# BLE112_Breakout_Board_v2_2.net
KiCad netlist of a schematic drawn in EAGLE
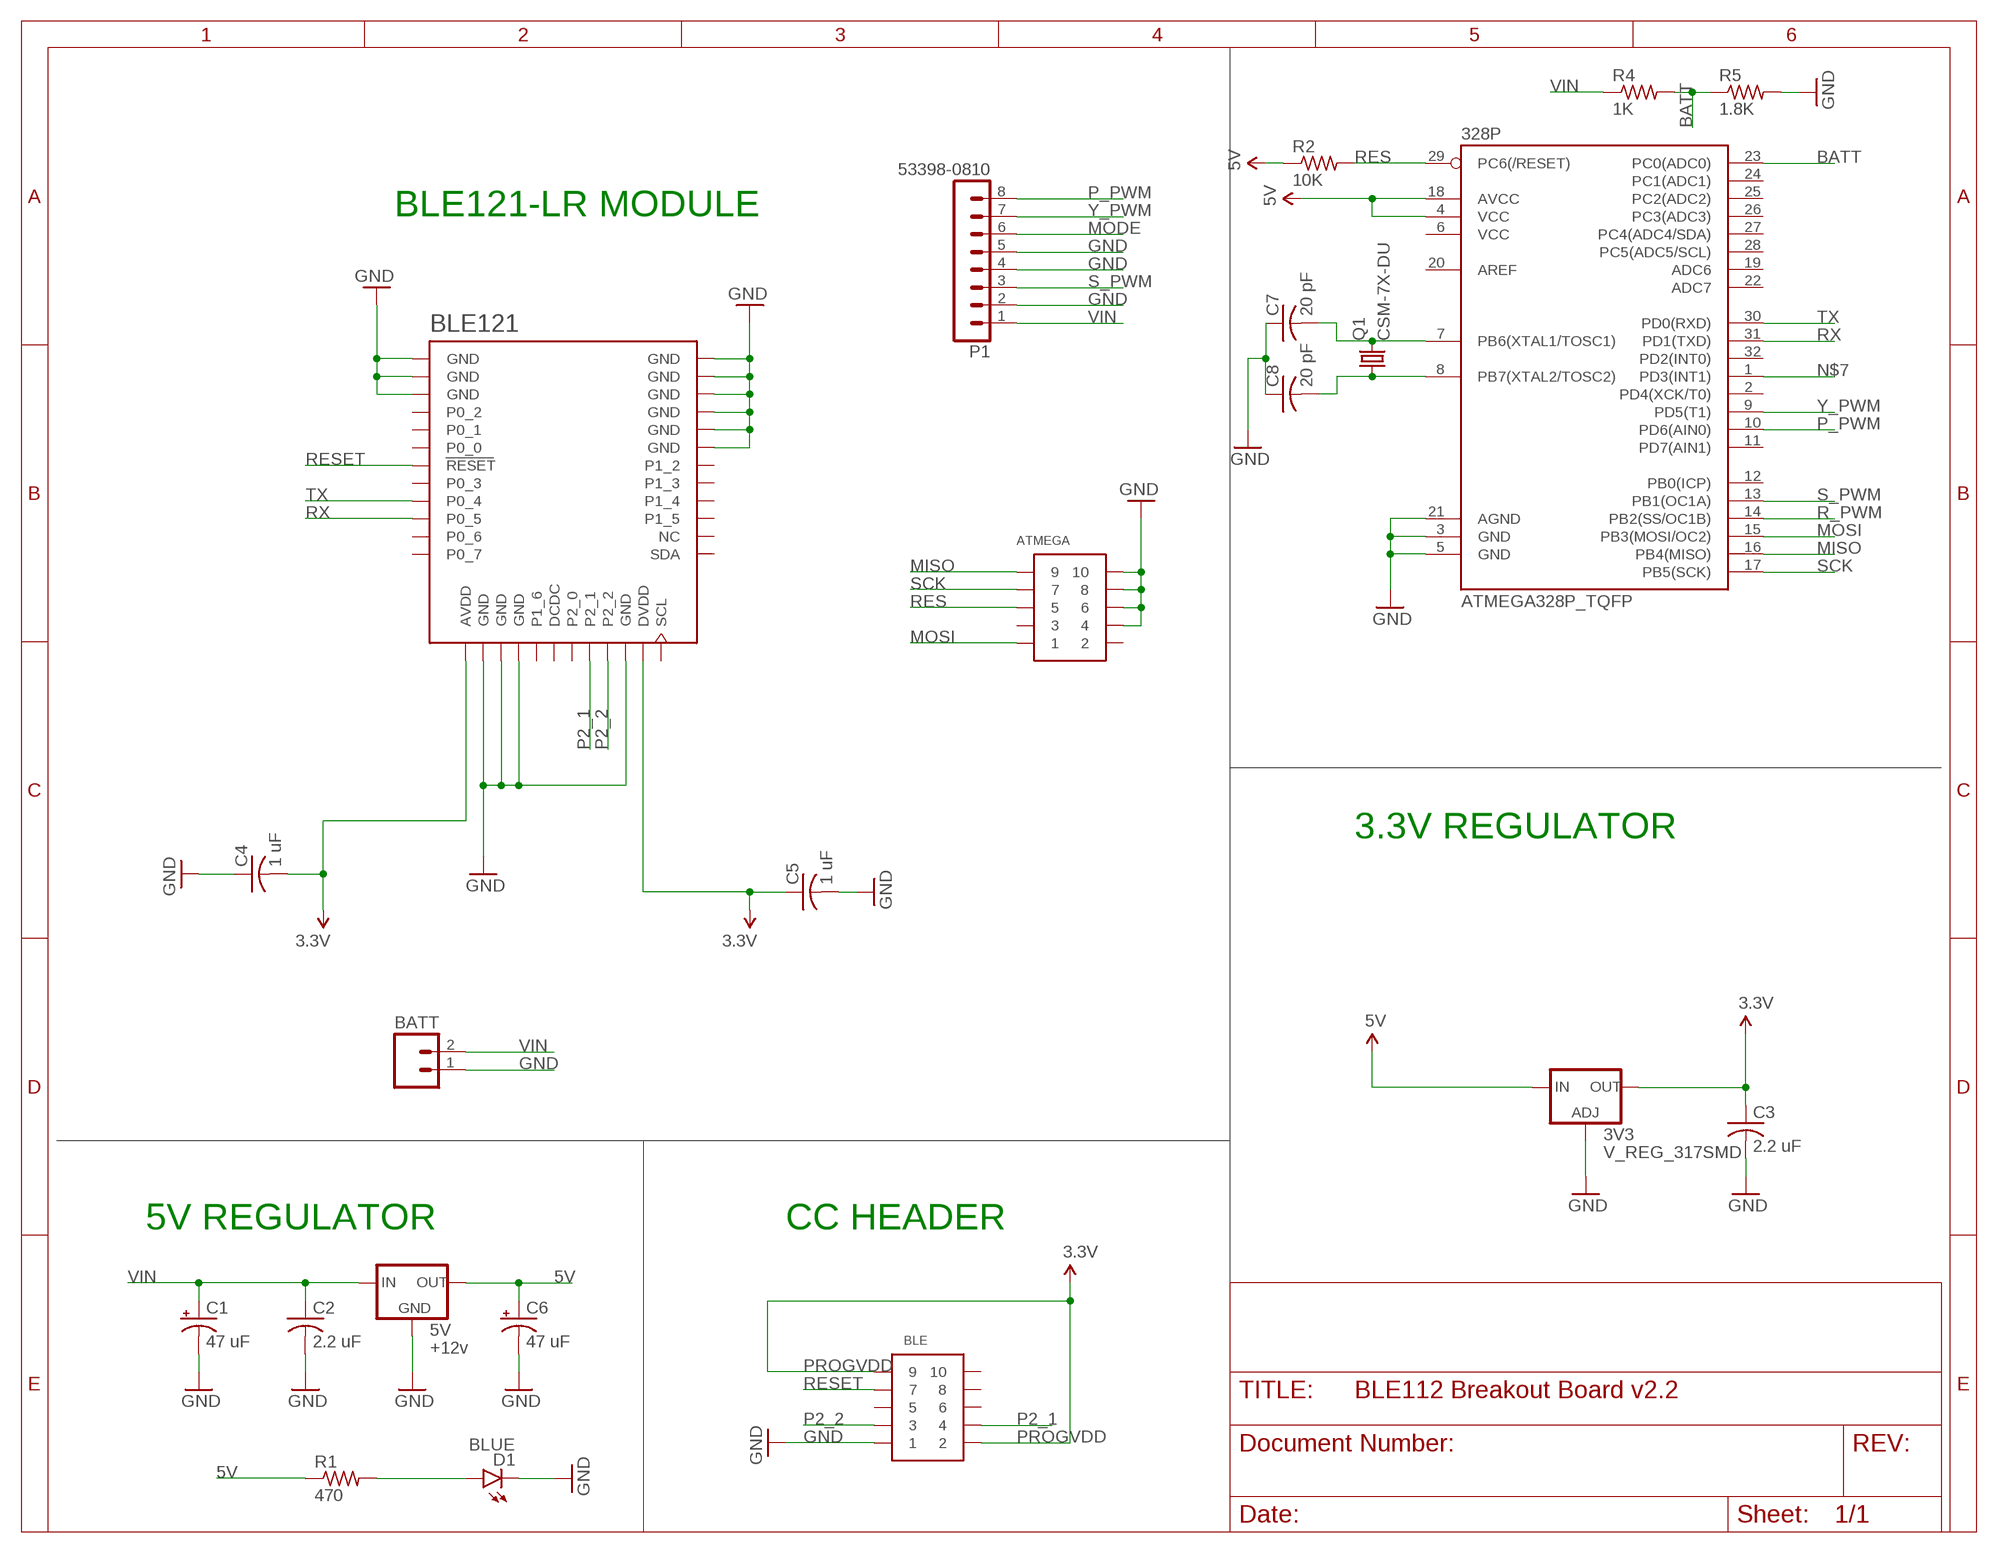
[diagram p0: schematic, sheet 1]

(export (version "E")
  (design (tool "Eeschema 10.0.6"))
  (components
    (comp (ref "3V3")
      (value "V_REG_317SMD")
      (footprint "eagle-import:SOT223")
      (libsource (lib "eagle-import") (part "V_REG_317SMD"))
    )
    (comp (ref "5V")
      (value "+12v")
      (footprint "eagle-import:TO-252")
      (libsource (lib "eagle-import") (part "V_REG_78XX7812"))
    )
    (comp (ref "328P")
      (value "ATMEGA328P_TQFP")
      (footprint "eagle-import:TQFP32-08")
      (libsource (lib "eagle-import") (part "ATMEGA328P_TQFP"))
    )
    (comp (ref "ATMEGA")
      (value "CONN_5-2-FTSH-V")
      (footprint "eagle-import:FTSH-105-DV")
      (libsource (lib "eagle-import") (part "CONN_5-2-FTSH-V"))
    )
    (comp (ref "BATT")
      (value "M02JST-PTH-2")
      (footprint "eagle-import:JST-2-PTH")
      (libsource (lib "eagle-import") (part "M02JST-PTH-2"))
    )
    (comp (ref "BLE")
      (value "CONN_5-2-FTSH-V")
      (footprint "eagle-import:FTSH-105-DV")
      (libsource (lib "eagle-import") (part "CONN_5-2-FTSH-V"))
    )
    (comp (ref "BLE121")
      (value "BLE121LR-VISUAL-A")
      (footprint "eagle-import:BLE121LR-A")
      (libsource (lib "eagle-import") (part "BLE121LR-VISUAL-A"))
    )
    (comp (ref "C1")
      (value "47 uF")
      (footprint "eagle-import:153CLV-0405")
      (libsource (lib "eagle-import") (part "CPOL-US153CLV-0405"))
    )
    (comp (ref "C2")
      (value "2.2 uF")
      (footprint "eagle-import:C0402")
      (libsource (lib "eagle-import") (part "C-USC0402"))
    )
    (comp (ref "C3")
      (value "2.2 uF")
      (footprint "eagle-import:C0402")
      (libsource (lib "eagle-import") (part "resistor_C-USC0402"))
    )
    (comp (ref "C4")
      (value "1 uF")
      (footprint "eagle-import:C0402")
      (libsource (lib "eagle-import") (part "resistor_C-USC0402"))
    )
    (comp (ref "C5")
      (value "1 uF")
      (footprint "eagle-import:C0402")
      (libsource (lib "eagle-import") (part "resistor_C-USC0402"))
    )
    (comp (ref "C6")
      (value "47 uF")
      (footprint "eagle-import:153CLV-0405")
      (libsource (lib "eagle-import") (part "CPOL-US153CLV-0405"))
    )
    (comp (ref "C7")
      (value "20 pF")
      (footprint "eagle-import:C0402")
      (libsource (lib "eagle-import") (part "C-USC0402"))
    )
    (comp (ref "C8")
      (value "20 pF")
      (footprint "eagle-import:C0402")
      (libsource (lib "eagle-import") (part "C-USC0402"))
    )
    (comp (ref "D1")
      (value "BLUE")
      (footprint "eagle-import:LED-0603")
      (libsource (lib "eagle-import") (part "LED-BLUE0603"))
    )
    (comp (ref "P1")
      (value "53398-0810")
      (footprint "eagle-import:53398-0810")
      (libsource (lib "eagle-import") (part "53398-0810"))
    )
    (comp (ref "Q1")
      (value "CSM-7X-DU")
      (footprint "eagle-import:CSM-7X-DU")
      (libsource (lib "eagle-import") (part "CSM-7X-DU"))
    )
    (comp (ref "R1")
      (value "470")
      (footprint "eagle-import:R0402")
      (libsource (lib "eagle-import") (part "resistor_R-US_R0402"))
    )
    (comp (ref "R2")
      (value "10K")
      (footprint "eagle-import:R0402")
      (libsource (lib "eagle-import") (part "R-US_R0402"))
    )
    (comp (ref "R4")
      (value "1K")
      (footprint "eagle-import:R0402")
      (libsource (lib "eagle-import") (part "R-US_R0402"))
    )
    (comp (ref "R5")
      (value "1.8K")
      (footprint "eagle-import:R0402")
      (libsource (lib "eagle-import") (part "R-US_R0402"))
    )
  )
  (nets
    (net (code "1") (name "/BATT") (class "Default")
      (node (ref "328P") (pin "23") (pinfunction "PC0(ADC0)_23") (pintype "bidirectional"))
      (node (ref "R4") (pin "2") (pinfunction "2_2") (pintype "passive"))
      (node (ref "R5") (pin "1") (pinfunction "1_1") (pintype "passive"))
    )
    (net (code "2") (name "/MISO") (class "Default")
      (node (ref "328P") (pin "16") (pinfunction "PB4(MISO)_16") (pintype "bidirectional"))
      (node (ref "ATMEGA") (pin "9") (pinfunction "9_9") (pintype "bidirectional"))
    )
    (net (code "3") (name "/MODE") (class "Default")
      (node (ref "P1") (pin "6") (pinfunction "6_6") (pintype "passive"))
    )
    (net (code "4") (name "/MOSI") (class "Default")
      (node (ref "328P") (pin "15") (pinfunction "PB3(MOSI/OC2)_15") (pintype "bidirectional"))
      (node (ref "ATMEGA") (pin "1") (pinfunction "1_1") (pintype "bidirectional"))
    )
    (net (code "5") (name "/N$7") (class "Default")
      (node (ref "328P") (pin "1") (pinfunction "PD3(INT1)_1") (pintype "bidirectional"))
    )
    (net (code "6") (name "/P2_1") (class "Default")
      (node (ref "BLE") (pin "4") (pinfunction "4_4") (pintype "bidirectional"))
      (node (ref "BLE121") (pin "P2_1") (pinfunction "P2_1_P2_1") (pintype "bidirectional"))
    )
    (net (code "7") (name "/P2_2") (class "Default")
      (node (ref "BLE") (pin "3") (pinfunction "3_3") (pintype "bidirectional"))
      (node (ref "BLE121") (pin "P2_2") (pinfunction "P2_2_P2_2") (pintype "bidirectional"))
    )
    (net (code "8") (name "/P_PWM") (class "Default")
      (node (ref "328P") (pin "10") (pinfunction "PD6(AIN0)_10") (pintype "bidirectional"))
      (node (ref "P1") (pin "8") (pinfunction "8_8") (pintype "passive"))
    )
    (net (code "9") (name "/RES") (class "Default")
      (node (ref "328P") (pin "29") (pinfunction "PC6(/RESET)_29") (pintype "bidirectional"))
      (node (ref "ATMEGA") (pin "5") (pinfunction "5_5") (pintype "bidirectional"))
      (node (ref "R2") (pin "2") (pinfunction "2_2") (pintype "passive"))
    )
    (net (code "10") (name "/RESET") (class "Default")
      (node (ref "BLE") (pin "7") (pinfunction "7_7") (pintype "bidirectional"))
      (node (ref "BLE121") (pin "RESET") (pinfunction "RESET_RESET") (pintype "input"))
    )
    (net (code "11") (name "/RX") (class "Default")
      (node (ref "328P") (pin "31") (pinfunction "PD1(TXD)_31") (pintype "bidirectional"))
      (node (ref "BLE121") (pin "P0_5") (pinfunction "P0_5_P0_5") (pintype "bidirectional"))
    )
    (net (code "12") (name "/R_PWM") (class "Default")
      (node (ref "328P") (pin "14") (pinfunction "PB2(SS/OC1B)_14") (pintype "bidirectional"))
    )
    (net (code "13") (name "/SCK") (class "Default")
      (node (ref "328P") (pin "17") (pinfunction "PB5(SCK)_17") (pintype "bidirectional"))
      (node (ref "ATMEGA") (pin "7") (pinfunction "7_7") (pintype "bidirectional"))
    )
    (net (code "14") (name "/S_PWM") (class "Default")
      (node (ref "328P") (pin "13") (pinfunction "PB1(OC1A)_13") (pintype "bidirectional"))
      (node (ref "P1") (pin "3") (pinfunction "3_3") (pintype "passive"))
    )
    (net (code "15") (name "/TX") (class "Default")
      (node (ref "328P") (pin "30") (pinfunction "PD0(RXD)_30") (pintype "bidirectional"))
      (node (ref "BLE121") (pin "P0_4") (pinfunction "P0_4_P0_4") (pintype "bidirectional"))
    )
    (net (code "16") (name "/VIN") (class "Default")
      (node (ref "5V") (pin "1") (pinfunction "IN_1") (pintype "input"))
      (node (ref "BATT") (pin "2") (pinfunction "2_2") (pintype "passive"))
      (node (ref "C1") (pin "+") (pinfunction "+_+") (pintype "passive"))
      (node (ref "C2") (pin "1") (pinfunction "1_1") (pintype "passive"))
      (node (ref "P1") (pin "1") (pinfunction "1_1") (pintype "passive"))
      (node (ref "R4") (pin "1") (pinfunction "1_1") (pintype "passive"))
    )
    (net (code "17") (name "/Y_PWM") (class "Default")
      (node (ref "328P") (pin "9") (pinfunction "PD5(T1)_9") (pintype "bidirectional"))
      (node (ref "P1") (pin "7") (pinfunction "7_7") (pintype "passive"))
    )
    (net (code "18") (name "3.3V") (class "Default")
      (node (ref "3V3") (pin "2") (pinfunction "OUT_2") (pintype "output"))
      (node (ref "BLE") (pin "2") (pinfunction "2_2") (pintype "bidirectional"))
      (node (ref "BLE") (pin "9") (pinfunction "9_9") (pintype "bidirectional"))
      (node (ref "BLE121") (pin "AVDD") (pinfunction "AVDD_AVDD") (pintype "power_in"))
      (node (ref "BLE121") (pin "DVDD") (pinfunction "DVDD_DVDD") (pintype "power_in"))
      (node (ref "C3") (pin "1") (pinfunction "1_1") (pintype "passive"))
      (node (ref "C4") (pin "2") (pinfunction "2_2") (pintype "passive"))
      (node (ref "C5") (pin "1") (pinfunction "1_1") (pintype "passive"))
    )
    (net (code "19") (name "5V") (class "Default")
      (node (ref "328P") (pin "18") (pinfunction "AVCC_18") (pintype "bidirectional"))
      (node (ref "328P") (pin "4") (pinfunction "VCC_4") (pintype "bidirectional"))
      (node (ref "3V3") (pin "3") (pinfunction "IN_3") (pintype "input"))
      (node (ref "5V") (pin "2") (pinfunction "OUT_2") (pintype "output"))
      (node (ref "C6") (pin "+") (pinfunction "+_+") (pintype "passive"))
      (node (ref "R1") (pin "1") (pinfunction "1_1") (pintype "passive"))
      (node (ref "R2") (pin "1") (pinfunction "1_1") (pintype "passive"))
    )
    (net (code "20") (name "GND") (class "Default")
      (node (ref "328P") (pin "21") (pinfunction "AGND_21") (pintype "bidirectional"))
      (node (ref "328P") (pin "3") (pinfunction "GND_3") (pintype "bidirectional"))
      (node (ref "328P") (pin "5") (pinfunction "GND_5") (pintype "bidirectional"))
      (node (ref "3V3") (pin "1") (pinfunction "ADJ_1") (pintype "input"))
      (node (ref "5V") (pin "3") (pinfunction "GND_3") (pintype "input"))
      (node (ref "ATMEGA") (pin "10") (pinfunction "10_10") (pintype "bidirectional"))
      (node (ref "ATMEGA") (pin "4") (pinfunction "4_4") (pintype "bidirectional"))
      (node (ref "ATMEGA") (pin "6") (pinfunction "6_6") (pintype "bidirectional"))
      (node (ref "ATMEGA") (pin "8") (pinfunction "8_8") (pintype "bidirectional"))
      (node (ref "BATT") (pin "1") (pinfunction "1_1") (pintype "passive"))
      (node (ref "BLE") (pin "1") (pinfunction "1_1") (pintype "bidirectional"))
      (node (ref "BLE121") (pin "GND") (pinfunction "GND_GND") (pintype "power_in"))
      (node (ref "BLE121") (pin "GND@10") (pinfunction "GND_GND@10") (pintype "power_in"))
      (node (ref "BLE121") (pin "GND@11") (pinfunction "GND_GND@11") (pintype "power_in"))
      (node (ref "BLE121") (pin "GND@12") (pinfunction "GND_GND@12") (pintype "power_in"))
      (node (ref "BLE121") (pin "GND@13") (pinfunction "GND_GND@13") (pintype "power_in"))
      (node (ref "BLE121") (pin "GND@2") (pinfunction "GND_GND@2") (pintype "power_in"))
      (node (ref "BLE121") (pin "GND@3") (pinfunction "GND_GND@3") (pintype "power_in"))
      (node (ref "BLE121") (pin "GND@4") (pinfunction "GND_GND@4") (pintype "power_in"))
      (node (ref "BLE121") (pin "GND@5") (pinfunction "GND_GND@5") (pintype "power_in"))
      (node (ref "BLE121") (pin "GND@6") (pinfunction "GND_GND@6") (pintype "power_in"))
      (node (ref "BLE121") (pin "GND@7") (pinfunction "GND_GND@7") (pintype "power_in"))
      (node (ref "BLE121") (pin "GND@8") (pinfunction "GND_GND@8") (pintype "power_in"))
      (node (ref "BLE121") (pin "GND@9") (pinfunction "GND_GND@9") (pintype "power_in"))
      (node (ref "C1") (pin "-") (pinfunction "-_-") (pintype "passive"))
      (node (ref "C2") (pin "2") (pinfunction "2_2") (pintype "passive"))
      (node (ref "C3") (pin "2") (pinfunction "2_2") (pintype "passive"))
      (node (ref "C4") (pin "1") (pinfunction "1_1") (pintype "passive"))
      (node (ref "C5") (pin "2") (pinfunction "2_2") (pintype "passive"))
      (node (ref "C6") (pin "-") (pinfunction "-_-") (pintype "passive"))
      (node (ref "C7") (pin "1") (pinfunction "1_1") (pintype "passive"))
      (node (ref "C8") (pin "1") (pinfunction "1_1") (pintype "passive"))
      (node (ref "D1") (pin "C") (pinfunction "C_C") (pintype "passive"))
      (node (ref "P1") (pin "2") (pinfunction "2_2") (pintype "passive"))
      (node (ref "P1") (pin "4") (pinfunction "4_4") (pintype "passive"))
      (node (ref "P1") (pin "5") (pinfunction "5_5") (pintype "passive"))
      (node (ref "R5") (pin "2") (pinfunction "2_2") (pintype "passive"))
    )
    (net (code "21") (name "Net-(328P-PB6(XTAL1{slash}TOSC1))") (class "Default")
      (node (ref "328P") (pin "7") (pinfunction "PB6(XTAL1/TOSC1)_7") (pintype "bidirectional"))
      (node (ref "C7") (pin "2") (pinfunction "2_2") (pintype "passive"))
      (node (ref "Q1") (pin "2") (pinfunction "2_2") (pintype "passive"))
    )
    (net (code "22") (name "Net-(328P-PB7(XTAL2{slash}TOSC2))") (class "Default")
      (node (ref "328P") (pin "8") (pinfunction "PB7(XTAL2/TOSC2)_8") (pintype "bidirectional"))
      (node (ref "C8") (pin "2") (pinfunction "2_2") (pintype "passive"))
      (node (ref "Q1") (pin "1") (pinfunction "1_1") (pintype "passive"))
    )
    (net (code "23") (name "Net-(D1-PadA)") (class "Default")
      (node (ref "D1") (pin "A") (pinfunction "A_A") (pintype "passive"))
      (node (ref "R1") (pin "2") (pinfunction "2_2") (pintype "passive"))
    )
    (net (code "24") (name "unconnected-(328P-ADC6-Pad19)") (class "Default")
      (node (ref "328P") (pin "19") (pinfunction "ADC6_19") (pintype "bidirectional"))
    )
    (net (code "25") (name "unconnected-(328P-ADC7-Pad22)") (class "Default")
      (node (ref "328P") (pin "22") (pinfunction "ADC7_22") (pintype "bidirectional"))
    )
    (net (code "26") (name "unconnected-(328P-AREF-Pad20)") (class "Default")
      (node (ref "328P") (pin "20") (pinfunction "AREF_20") (pintype "bidirectional"))
    )
    (net (code "27") (name "unconnected-(328P-PB0(ICP)-Pad12)") (class "Default")
      (node (ref "328P") (pin "12") (pinfunction "PB0(ICP)_12") (pintype "bidirectional"))
    )
    (net (code "28") (name "unconnected-(328P-PC1(ADC1)-Pad24)") (class "Default")
      (node (ref "328P") (pin "24") (pinfunction "PC1(ADC1)_24") (pintype "bidirectional"))
    )
    (net (code "29") (name "unconnected-(328P-PC2(ADC2)-Pad25)") (class "Default")
      (node (ref "328P") (pin "25") (pinfunction "PC2(ADC2)_25") (pintype "bidirectional"))
    )
    (net (code "30") (name "unconnected-(328P-PC3(ADC3)-Pad26)") (class "Default")
      (node (ref "328P") (pin "26") (pinfunction "PC3(ADC3)_26") (pintype "bidirectional"))
    )
    (net (code "31") (name "unconnected-(328P-PC4(ADC4{slash}SDA)-Pad27)") (class "Default")
      (node (ref "328P") (pin "27") (pinfunction "PC4(ADC4/SDA)_27") (pintype "bidirectional"))
    )
    (net (code "32") (name "unconnected-(328P-PC5(ADC5{slash}SCL)-Pad28)") (class "Default")
      (node (ref "328P") (pin "28") (pinfunction "PC5(ADC5/SCL)_28") (pintype "bidirectional"))
    )
    (net (code "33") (name "unconnected-(328P-PD2(INT0)-Pad32)") (class "Default")
      (node (ref "328P") (pin "32") (pinfunction "PD2(INT0)_32") (pintype "bidirectional"))
    )
    (net (code "34") (name "unconnected-(328P-PD4(XCK{slash}T0)-Pad2)") (class "Default")
      (node (ref "328P") (pin "2") (pinfunction "PD4(XCK/T0)_2") (pintype "bidirectional"))
    )
    (net (code "35") (name "unconnected-(328P-PD7(AIN1)-Pad11)") (class "Default")
      (node (ref "328P") (pin "11") (pinfunction "PD7(AIN1)_11") (pintype "bidirectional"))
    )
    (net (code "36") (name "unconnected-(328P-VCC-Pad6)") (class "Default")
      (node (ref "328P") (pin "6") (pinfunction "VCC_6") (pintype "bidirectional"))
    )
    (net (code "37") (name "unconnected-(ATMEGA-Pad2)") (class "Default")
      (node (ref "ATMEGA") (pin "2") (pinfunction "2_2") (pintype "bidirectional"))
    )
    (net (code "38") (name "unconnected-(ATMEGA-Pad3)") (class "Default")
      (node (ref "ATMEGA") (pin "3") (pinfunction "3_3") (pintype "bidirectional"))
    )
    (net (code "39") (name "unconnected-(BLE-Pad5)") (class "Default")
      (node (ref "BLE") (pin "5") (pinfunction "5_5") (pintype "bidirectional"))
    )
    (net (code "40") (name "unconnected-(BLE-Pad6)") (class "Default")
      (node (ref "BLE") (pin "6") (pinfunction "6_6") (pintype "bidirectional"))
    )
    (net (code "41") (name "unconnected-(BLE-Pad8)") (class "Default")
      (node (ref "BLE") (pin "8") (pinfunction "8_8") (pintype "bidirectional"))
    )
    (net (code "42") (name "unconnected-(BLE-Pad10)") (class "Default")
      (node (ref "BLE") (pin "10") (pinfunction "10_10") (pintype "bidirectional"))
    )
    (net (code "43") (name "unconnected-(BLE121-PadDCDC)") (class "Default")
      (node (ref "BLE121") (pin "DCDC") (pinfunction "DCDC_DCDC") (pintype "bidirectional"))
    )
    (net (code "44") (name "unconnected-(BLE121-PadNC)") (class "Default")
      (node (ref "BLE121") (pin "NC") (pinfunction "NC_NC") (pintype "no_connect"))
    )
    (net (code "45") (name "unconnected-(BLE121-PadP0_0)") (class "Default")
      (node (ref "BLE121") (pin "P0_0") (pinfunction "P0_0_P0_0") (pintype "bidirectional"))
    )
    (net (code "46") (name "unconnected-(BLE121-PadP0_1)") (class "Default")
      (node (ref "BLE121") (pin "P0_1") (pinfunction "P0_1_P0_1") (pintype "bidirectional"))
    )
    (net (code "47") (name "unconnected-(BLE121-PadP0_2)") (class "Default")
      (node (ref "BLE121") (pin "P0_2") (pinfunction "P0_2_P0_2") (pintype "bidirectional"))
    )
    (net (code "48") (name "unconnected-(BLE121-PadP0_3)") (class "Default")
      (node (ref "BLE121") (pin "P0_3") (pinfunction "P0_3_P0_3") (pintype "bidirectional"))
    )
    (net (code "49") (name "unconnected-(BLE121-PadP0_6)") (class "Default")
      (node (ref "BLE121") (pin "P0_6") (pinfunction "P0_6_P0_6") (pintype "bidirectional"))
    )
    (net (code "50") (name "unconnected-(BLE121-PadP0_7)") (class "Default")
      (node (ref "BLE121") (pin "P0_7") (pinfunction "P0_7_P0_7") (pintype "bidirectional"))
    )
    (net (code "51") (name "unconnected-(BLE121-PadP1_2)") (class "Default")
      (node (ref "BLE121") (pin "P1_2") (pinfunction "P1_2_P1_2") (pintype "bidirectional"))
    )
    (net (code "52") (name "unconnected-(BLE121-PadP1_3)") (class "Default")
      (node (ref "BLE121") (pin "P1_3") (pinfunction "P1_3_P1_3") (pintype "bidirectional"))
    )
    (net (code "53") (name "unconnected-(BLE121-PadP1_4)") (class "Default")
      (node (ref "BLE121") (pin "P1_4") (pinfunction "P1_4_P1_4") (pintype "bidirectional"))
    )
    (net (code "54") (name "unconnected-(BLE121-PadP1_5)") (class "Default")
      (node (ref "BLE121") (pin "P1_5") (pinfunction "P1_5_P1_5") (pintype "bidirectional"))
    )
    (net (code "55") (name "unconnected-(BLE121-PadP1_6)") (class "Default")
      (node (ref "BLE121") (pin "P1_6") (pinfunction "P1_6_P1_6") (pintype "bidirectional"))
    )
    (net (code "56") (name "unconnected-(BLE121-PadP2_0)") (class "Default")
      (node (ref "BLE121") (pin "P2_0") (pinfunction "P2_0_P2_0") (pintype "bidirectional"))
    )
    (net (code "57") (name "unconnected-(BLE121-PadSCL)") (class "Default")
      (node (ref "BLE121") (pin "SCL") (pinfunction "SCL_SCL") (pintype "bidirectional"))
    )
    (net (code "58") (name "unconnected-(BLE121-PadSDA)") (class "Default")
      (node (ref "BLE121") (pin "SDA") (pinfunction "SDA_SDA") (pintype "bidirectional"))
    )
  )
)
